# ProgrammableAttenuator.net
KiCad netlist of a schematic drawn in Altium Designer
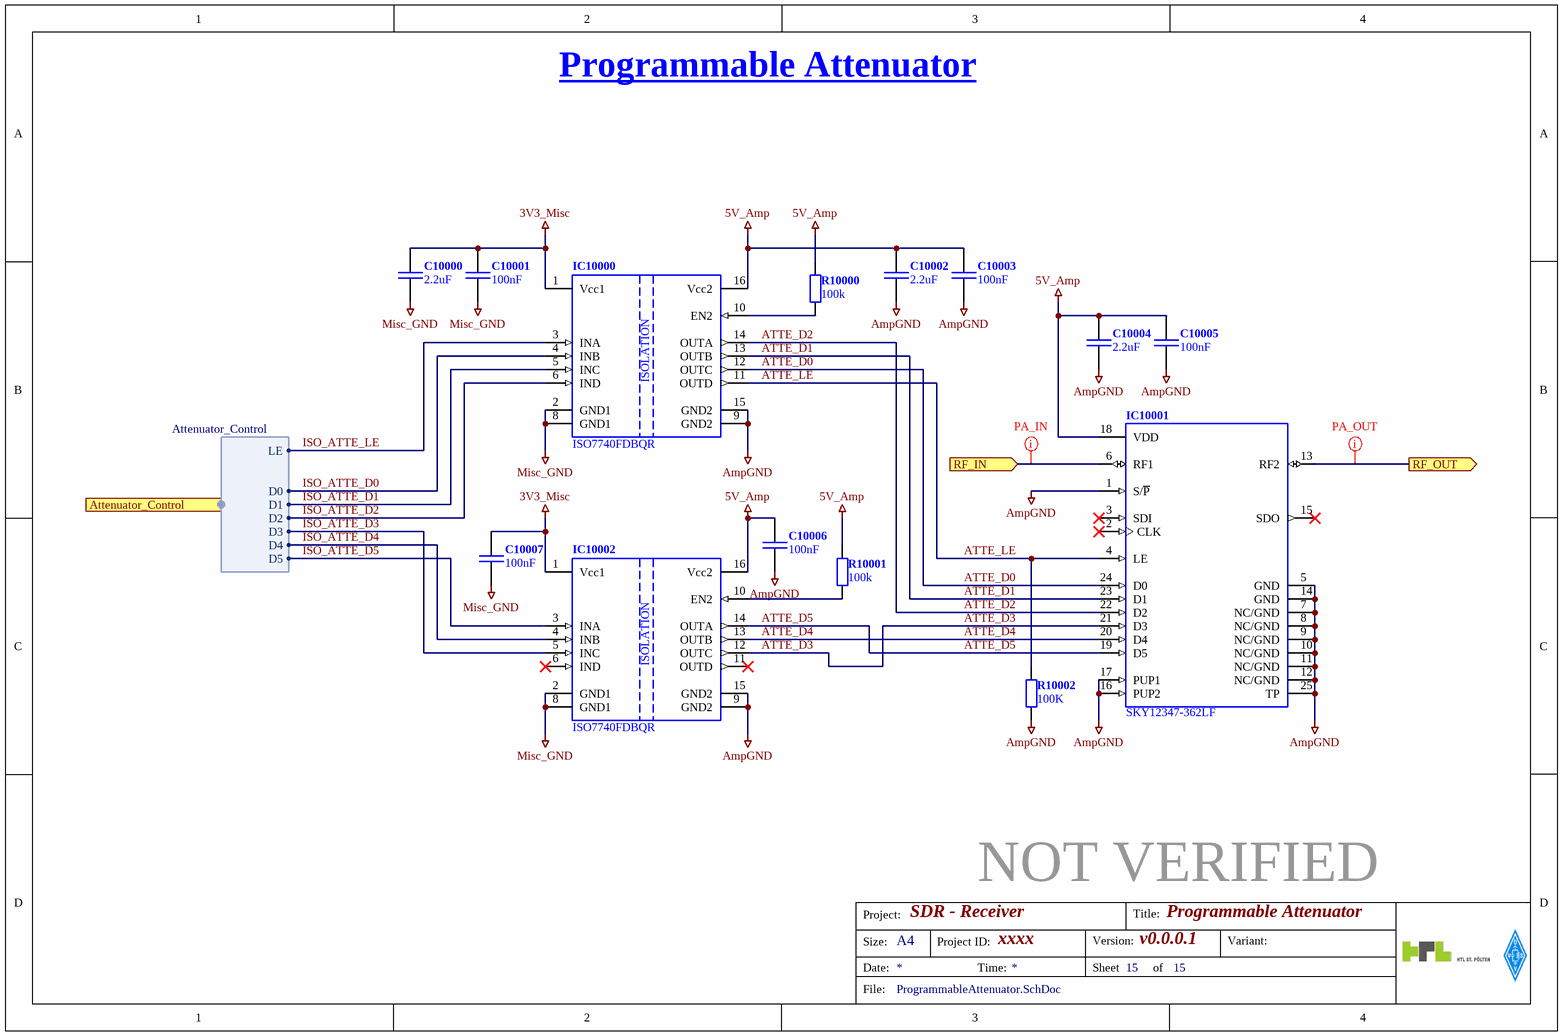
[diagram p0: ProgrammableAttenuator.SchDoc]

(export (version "E")
  (design (tool "Eeschema 10.0.6"))
  (components
    (comp (ref "C10000")
      (value "2.2uF")
      (footprint "PrometheusLib:C_0805_N [CAPC2013N IPC]")
      (libsource (lib "PrometheusLib") (part "C_GENERIC"))
    )
    (comp (ref "C10001")
      (value "100nF")
      (footprint "PrometheusLib:C_0603_N [CAPC1608N IPC]")
      (libsource (lib "PrometheusLib") (part "C_GENERIC"))
    )
    (comp (ref "C10002")
      (value "2.2uF")
      (footprint "PrometheusLib:C_0805_N [CAPC2013N IPC]")
      (libsource (lib "PrometheusLib") (part "C_GENERIC"))
    )
    (comp (ref "C10003")
      (value "100nF")
      (footprint "PrometheusLib:C_0603_N [CAPC1608N IPC]")
      (libsource (lib "PrometheusLib") (part "C_GENERIC"))
    )
    (comp (ref "C10004")
      (value "2.2uF")
      (footprint "PrometheusLib:C_0805_N [CAPC2013N IPC]")
      (libsource (lib "PrometheusLib") (part "C_GENERIC"))
    )
    (comp (ref "C10005")
      (value "100nF")
      (footprint "PrometheusLib:C_0603_N [CAPC1608N IPC]")
      (libsource (lib "PrometheusLib") (part "C_GENERIC"))
    )
    (comp (ref "C10006")
      (value "100nF")
      (footprint "PrometheusLib:C_0603_N [CAPC1608N IPC]")
      (libsource (lib "PrometheusLib") (part "C_GENERIC"))
    )
    (comp (ref "C10007")
      (value "100nF")
      (footprint "PrometheusLib:C_0603_N [CAPC1608N IPC]")
      (libsource (lib "PrometheusLib") (part "C_GENERIC"))
    )
    (comp (ref "IC10000")
      (value "ISO7740FDBQR")
      (footprint "SOP64P600X175-16N IPC")
      (libsource (lib "PrometheusLib") (part "IC_ISO7740FDBQR"))
    )
    (comp (ref "IC10001")
      (value "SKY12347-362LF")
      (footprint "QFN50P400X400X100_HS-25N IPC")
      (description "Six-Bit Digital Attenuator\r\nAttenuation: 0.5 dB ... 31.5 dB\r\nSerial or Parallel Driver")
      (libsource (lib "PrometheusLib") (part "IC_SKY12347-362LF"))
    )
    (comp (ref "IC10002")
      (value "ISO7740FDBQR")
      (footprint "SOP64P600X175-16N IPC")
      (libsource (lib "PrometheusLib") (part "IC_ISO7740FDBQR"))
    )
    (comp (ref "R10000")
      (value "100k")
      (footprint "PrometheusLib:R_0603_N [RESC1608N IPC]")
      (libsource (lib "PrometheusLib") (part "R_GENERIC_DIN"))
    )
    (comp (ref "R10001")
      (value "100k")
      (footprint "PrometheusLib:R_0603_N [RESC1608N IPC]")
      (libsource (lib "PrometheusLib") (part "R_GENERIC_DIN"))
    )
    (comp (ref "R10002")
      (value "100K")
      (footprint "PrometheusLib:R_0603_N [RESC1608N IPC]")
      (libsource (lib "PrometheusLib") (part "R_GENERIC_DIN"))
    )
  )
  (nets
    (net (code "2") (name "/ATTE_D0") (class "Default")
      (node (ref "IC10000") (pin "12") (pinfunction "OUTC_12") (pintype "output"))
      (node (ref "IC10001") (pin "24") (pinfunction "D0_24") (pintype "input"))
    )
    (net (code "3") (name "/ATTE_D1") (class "Default")
      (node (ref "IC10000") (pin "13") (pinfunction "OUTB_13") (pintype "output"))
      (node (ref "IC10001") (pin "23") (pinfunction "D1_23") (pintype "input"))
    )
    (net (code "4") (name "/ATTE_D2") (class "Default")
      (node (ref "IC10000") (pin "14") (pinfunction "OUTA_14") (pintype "output"))
      (node (ref "IC10001") (pin "22") (pinfunction "D2_22") (pintype "input"))
    )
    (net (code "5") (name "/ATTE_D3") (class "Default")
      (node (ref "IC10001") (pin "21") (pinfunction "D3_21") (pintype "input"))
      (node (ref "IC10002") (pin "12") (pinfunction "OUTC_12") (pintype "output"))
    )
    (net (code "6") (name "/ATTE_D4") (class "Default")
      (node (ref "IC10001") (pin "20") (pinfunction "D4_20") (pintype "input"))
      (node (ref "IC10002") (pin "13") (pinfunction "OUTB_13") (pintype "output"))
    )
    (net (code "7") (name "/ATTE_D5") (class "Default")
      (node (ref "IC10001") (pin "19") (pinfunction "D5_19") (pintype "input"))
      (node (ref "IC10002") (pin "14") (pinfunction "OUTA_14") (pintype "output"))
    )
    (net (code "8") (name "/ATTE_LE") (class "Default")
      (node (ref "IC10000") (pin "11") (pinfunction "OUTD_11") (pintype "output"))
      (node (ref "IC10001") (pin "4") (pinfunction "LE_4") (pintype "input"))
      (node (ref "R10002") (pin "2") (pinfunction "2_2") (pintype "passive"))
    )
    (net (code "9") (name "/ISO_ATTE_D0") (class "Default")
      (node (ref "IC10000") (pin "4") (pinfunction "INB_4") (pintype "input"))
    )
    (net (code "10") (name "/ISO_ATTE_D1") (class "Default")
      (node (ref "IC10000") (pin "5") (pinfunction "INC_5") (pintype "input"))
    )
    (net (code "11") (name "/ISO_ATTE_D2") (class "Default")
      (node (ref "IC10000") (pin "6") (pinfunction "IND_6") (pintype "input"))
    )
    (net (code "12") (name "/ISO_ATTE_D3") (class "Default")
      (node (ref "IC10002") (pin "5") (pinfunction "INC_5") (pintype "input"))
    )
    (net (code "13") (name "/ISO_ATTE_D4") (class "Default")
      (node (ref "IC10002") (pin "4") (pinfunction "INB_4") (pintype "input"))
    )
    (net (code "14") (name "/ISO_ATTE_D5") (class "Default")
      (node (ref "IC10002") (pin "3") (pinfunction "INA_3") (pintype "input"))
    )
    (net (code "15") (name "/ISO_ATTE_LE") (class "Default")
      (node (ref "IC10000") (pin "3") (pinfunction "INA_3") (pintype "input"))
    )
    (net (code "16") (name "/RF_IN") (class "Default")
      (node (ref "IC10001") (pin "6") (pinfunction "RF1_6") (pintype "bidirectional"))
    )
    (net (code "17") (name "/RF_OUT") (class "Default")
      (node (ref "IC10001") (pin "13") (pinfunction "RF2_13") (pintype "bidirectional"))
    )
    (net (code "19") (name "3V3_Misc") (class "Default")
      (node (ref "C10000") (pin "1") (pintype "passive"))
      (node (ref "C10001") (pin "1") (pintype "passive"))
      (node (ref "C10007") (pin "1") (pintype "passive"))
      (node (ref "IC10000") (pin "1") (pinfunction "Vcc1_1") (pintype "passive"))
      (node (ref "IC10002") (pin "1") (pinfunction "Vcc1_1") (pintype "passive"))
    )
    (net (code "20") (name "5V_Amp") (class "Default")
      (node (ref "C10002") (pin "1") (pintype "passive"))
      (node (ref "C10003") (pin "1") (pintype "passive"))
      (node (ref "C10004") (pin "1") (pintype "passive"))
      (node (ref "C10005") (pin "1") (pintype "passive"))
      (node (ref "C10006") (pin "1") (pintype "passive"))
      (node (ref "IC10000") (pin "16") (pinfunction "Vcc2_16") (pintype "passive"))
      (node (ref "IC10001") (pin "18") (pinfunction "VDD_18") (pintype "power_in"))
      (node (ref "IC10002") (pin "16") (pinfunction "Vcc2_16") (pintype "passive"))
      (node (ref "R10000") (pin "2") (pinfunction "2_2") (pintype "passive"))
      (node (ref "R10001") (pin "2") (pinfunction "2_2") (pintype "passive"))
    )
    (net (code "21") (name "AmpGND") (class "Default")
      (node (ref "C10002") (pin "2") (pintype "passive"))
      (node (ref "C10003") (pin "2") (pintype "passive"))
      (node (ref "C10004") (pin "2") (pintype "passive"))
      (node (ref "C10005") (pin "2") (pintype "passive"))
      (node (ref "C10006") (pin "2") (pintype "passive"))
      (node (ref "IC10000") (pin "15") (pinfunction "GND2_15") (pintype "passive"))
      (node (ref "IC10000") (pin "9") (pinfunction "GND2_9") (pintype "passive"))
      (node (ref "IC10001") (pin "1") (pinfunction "S/~{P}_1") (pintype "input"))
      (node (ref "IC10001") (pin "10") (pinfunction "NC/GND_10") (pintype "power_in"))
      (node (ref "IC10001") (pin "11") (pinfunction "NC/GND_11") (pintype "power_in"))
      (node (ref "IC10001") (pin "12") (pinfunction "NC/GND_12") (pintype "power_in"))
      (node (ref "IC10001") (pin "14") (pinfunction "GND_14") (pintype "passive"))
      (node (ref "IC10001") (pin "16") (pinfunction "PUP2_16") (pintype "input"))
      (node (ref "IC10001") (pin "17") (pinfunction "PUP1_17") (pintype "input"))
      (node (ref "IC10001") (pin "25") (pinfunction "TP_25") (pintype "power_in"))
      (node (ref "IC10001") (pin "5") (pinfunction "GND_5") (pintype "power_in"))
      (node (ref "IC10001") (pin "7") (pinfunction "NC/GND_7") (pintype "power_in"))
      (node (ref "IC10001") (pin "8") (pinfunction "NC/GND_8") (pintype "power_in"))
      (node (ref "IC10001") (pin "9") (pinfunction "NC/GND_9") (pintype "power_in"))
      (node (ref "IC10002") (pin "15") (pinfunction "GND2_15") (pintype "passive"))
      (node (ref "IC10002") (pin "9") (pinfunction "GND2_9") (pintype "passive"))
      (node (ref "R10002") (pin "1") (pinfunction "1_1") (pintype "passive"))
    )
    (net (code "22") (name "Misc_GND") (class "Default")
      (node (ref "C10000") (pin "2") (pintype "passive"))
      (node (ref "C10001") (pin "2") (pintype "passive"))
      (node (ref "C10007") (pin "2") (pintype "passive"))
      (node (ref "IC10000") (pin "2") (pinfunction "GND1_2") (pintype "passive"))
      (node (ref "IC10000") (pin "8") (pinfunction "GND1_8") (pintype "passive"))
      (node (ref "IC10002") (pin "2") (pinfunction "GND1_2") (pintype "passive"))
      (node (ref "IC10002") (pin "8") (pinfunction "GND1_8") (pintype "passive"))
    )
    (net (code "23") (name "Net-(IC10000-EN2)") (class "Default")
      (node (ref "IC10000") (pin "10") (pinfunction "EN2_10") (pintype "input"))
      (node (ref "R10000") (pin "1") (pinfunction "1_1") (pintype "passive"))
    )
    (net (code "24") (name "Net-(IC10002-EN2)") (class "Default")
      (node (ref "IC10002") (pin "10") (pinfunction "EN2_10") (pintype "input"))
      (node (ref "R10001") (pin "1") (pinfunction "1_1") (pintype "passive"))
    )
    (net (code "25") (name "unconnected-(IC10001-CLK-Pad2)") (class "Default")
      (node (ref "IC10001") (pin "2") (pinfunction "CLK_2") (pintype "input+no_connect"))
    )
    (net (code "26") (name "unconnected-(IC10001-SDI-Pad3)") (class "Default")
      (node (ref "IC10001") (pin "3") (pinfunction "SDI_3") (pintype "input+no_connect"))
    )
    (net (code "27") (name "unconnected-(IC10001-SDO-Pad15)") (class "Default")
      (node (ref "IC10001") (pin "15") (pinfunction "SDO_15") (pintype "output+no_connect"))
    )
    (net (code "28") (name "unconnected-(IC10002-IND-Pad6)") (class "Default")
      (node (ref "IC10002") (pin "6") (pinfunction "IND_6") (pintype "input+no_connect"))
    )
    (net (code "29") (name "unconnected-(IC10002-OUTD-Pad11)") (class "Default")
      (node (ref "IC10002") (pin "11") (pinfunction "OUTD_11") (pintype "output+no_connect"))
    )
  )
)
